# 3_3V_Buck_Schematic.net
KiCad netlist of a schematic drawn in Altium Designer
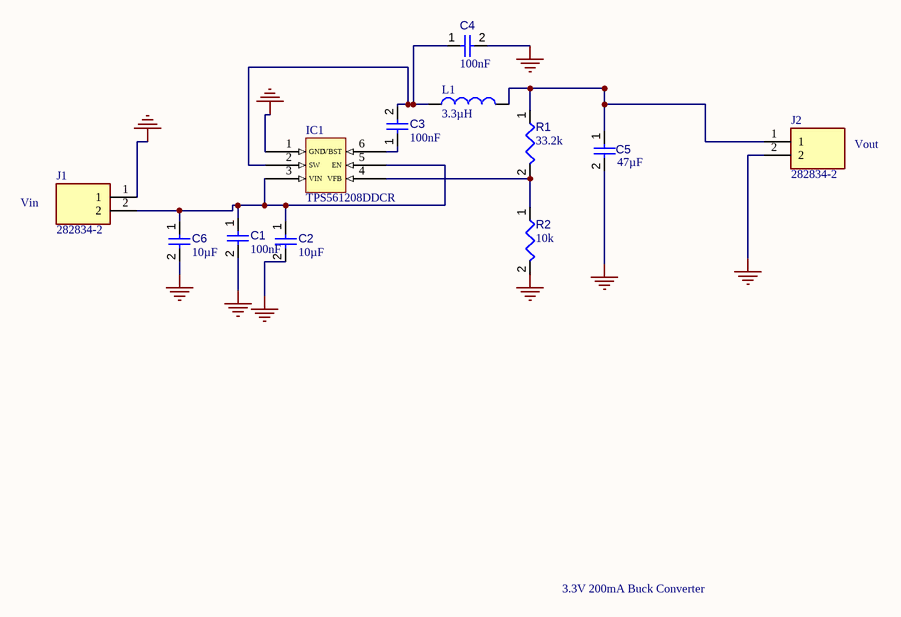
[diagram p0: 3.3V_Buck_Schematic.SchDoc]

(export (version "E")
  (design (tool "Eeschema 10.0.6"))
  (components
    (comp (ref "C1")
      (value "100nF")
      (footprint "CAPC1005X56X25LL10T15")
      (description "Chip Capacitor, 0.1 uF, +/- 5%, 16 V, 0402 (1005 Metric)")
      (fields (field (name "TOLERANCE") "5%") (field (name "Comment") "Capacitor 0.1 uF +/- 5% 16 V 0402"))
      (libsource (lib "Joshua Teele") (part "CAP-NP-2"))
    )
    (comp (ref "C2")
      (value "10µF")
      (footprint "CAPC2012X14N")
      (fields (field (name "Comment") "MSAST21GBB5106MTNA01"))
      (libsource (lib "Joshua Teele") (part "CAP-NP-2"))
    )
    (comp (ref "C3")
      (value "100nF")
      (footprint "CAPC2012X06N")
      (description "0805 100 nF 25V ±10 % Tolerance X7R Surface Mount Multilayer Ceramic Capacitor")
      (fields (field (name "TOLERANCE") "10%") (field (name "Comment") "08053C104KAT2A"))
      (libsource (lib "Joshua Teele") (part "CAP-NP-2"))
    )
    (comp (ref "C4")
      (value "100nF")
      (footprint "CAPC1005X56X25LL10T15")
      (description "Chip Capacitor, 0.1 uF, +/- 5%, 16 V, 0402 (1005 Metric)")
      (fields (field (name "TOLERANCE") "5%") (field (name "Comment") "Capacitor 0.1 uF +/- 5% 16 V 0402"))
      (libsource (lib "Joshua Teele") (part "CAP-NP-2"))
    )
    (comp (ref "C5")
      (value "47µF")
      (footprint "CAPC3225X27N")
      (description "Capacitor: ceramic; MLCC; 47uF; 16V; X5R; ±10%; SMD; 1210; Series: GRM")
      (fields (field (name "VOLTAGE") "16V") (field (name "TOLERANCE") "10%"))
      (libsource (lib "Joshua Teele") (part "CAP-NP-2"))
    )
    (comp (ref "C6")
      (value "10µF")
      (footprint "CAPC2012X14N")
      (fields (field (name "Comment") "MSAST21GBB5106MTNA01"))
      (libsource (lib "Joshua Teele") (part "CAP-NP-2"))
    )
    (comp (ref "IC1")
      (value "TPS561208DDCR")
      (footprint "SOT95P245X110-6N")
      (description "4.5V to 17V Input, 1A Output, Synchronous Step-Down Converter 6-SOT-23-THIN -40 to 125")
      (libsource (lib "Joshua Teele") (part "TPS561208DDCR-Symbol-1"))
    )
    (comp (ref "J1")
      (value "282834-2")
      (footprint "TE_282834-2")
      (description "Terminal Block Connector PCB 2.54 mm 30-16 AWG Green 10 A 150 V M1.6")
      (fields (field (name "MF") "TE Connectivity"))
      (libsource (lib "") (part "282834-2_1"))
    )
    (comp (ref "J2")
      (value "282834-2")
      (footprint "TE_282834-2")
      (description "Terminal Block Connector PCB 2.54 mm 30-16 AWG Green 10 A 150 V M1.6")
      (fields (field (name "MF") "TE Connectivity"))
      (libsource (lib "Joshua Teele") (part "282834-2"))
    )
    (comp (ref "L1")
      (value "3.3µH")
      (footprint "INDP3225X24N")
      (description "Inductor Power Unshielded Wirewound 3.3uH 20% 7.96MHz 15Q-Factor Ferrite 1A 192mOhm DCR 1210 T/R")
      (fields (field (name "TOLERANCE") "20%") (field (name "Comment") "NLCV32T-3R3M-PFR"))
      (libsource (lib "Joshua Teele") (part "IND-2"))
    )
    (comp (ref "R1")
      (value "33.2k")
      (footprint "CAPC2012X07N")
      (description "Res Thick Film 0805 33.2K Ohm 1% 0.125W(1/8W) ±100ppm/°C Molded SMD Punched Carrier T/R")
      (fields (field (name "TOLERANCE") "1%") (field (name "Comment") "ERJ-6ENF3322V"))
      (libsource (lib "Joshua Teele") (part "RES-2"))
    )
    (comp (ref "R2")
      (value "10k")
      (footprint "RESC3216X60X45ML15T20")
      (description "Chip Resistor, 10 KOhm, +/- 1%, 0.25 W, -55 to 155 degC, 1206 (3216 Metric)")
      (fields (field (name "TOLERANCE") "1%") (field (name "POWER") "250mW"))
      (libsource (lib "Joshua Teele") (part "RES-2"))
    )
  )
  (nets
    (net (code "1") (name "GND") (class "Default")
      (node (ref "C1") (pin "2") (pinfunction "2_2") (pintype "passive"))
      (node (ref "C2") (pin "2") (pinfunction "2_2") (pintype "passive"))
      (node (ref "C4") (pin "2") (pinfunction "2_2") (pintype "passive"))
      (node (ref "C5") (pin "2") (pinfunction "2_2") (pintype "passive"))
      (node (ref "C6") (pin "2") (pinfunction "2_2") (pintype "passive"))
      (node (ref "IC1") (pin "1") (pinfunction "GND_1") (pintype "input"))
      (node (ref "J1") (pin "1") (pinfunction "1_1") (pintype "passive"))
      (node (ref "J2") (pin "2") (pinfunction "2_2") (pintype "passive"))
      (node (ref "R2") (pin "2") (pinfunction "2_2") (pintype "passive"))
    )
    (net (code "2") (name "Net-(C5-Pad1)") (class "Default")
      (node (ref "C5") (pin "1") (pinfunction "1_1") (pintype "passive"))
      (node (ref "J2") (pin "1") (pinfunction "1_1") (pintype "passive"))
      (node (ref "L1") (pin "2") (pinfunction "2_2") (pintype "passive"))
      (node (ref "R1") (pin "1") (pinfunction "1_1") (pintype "passive"))
    )
    (net (code "3") (name "Net-(IC1-EN)") (class "Default")
      (node (ref "C1") (pin "1") (pinfunction "1_1") (pintype "passive"))
      (node (ref "C2") (pin "1") (pinfunction "1_1") (pintype "passive"))
      (node (ref "C6") (pin "1") (pinfunction "1_1") (pintype "passive"))
      (node (ref "IC1") (pin "3") (pinfunction "VIN_3") (pintype "input"))
      (node (ref "IC1") (pin "5") (pinfunction "EN_5") (pintype "input"))
      (node (ref "J1") (pin "2") (pinfunction "2_2") (pintype "passive"))
    )
    (net (code "4") (name "Net-(IC1-SW)") (class "Default")
      (node (ref "C3") (pin "2") (pinfunction "2_2") (pintype "passive"))
      (node (ref "C4") (pin "1") (pinfunction "1_1") (pintype "passive"))
      (node (ref "IC1") (pin "2") (pinfunction "SW_2") (pintype "input"))
      (node (ref "L1") (pin "1") (pinfunction "1_1") (pintype "passive"))
    )
    (net (code "5") (name "Net-(IC1-VBST)") (class "Default")
      (node (ref "C3") (pin "1") (pinfunction "1_1") (pintype "passive"))
      (node (ref "IC1") (pin "6") (pinfunction "VBST_6") (pintype "input"))
    )
    (net (code "6") (name "Net-(IC1-VFB)") (class "Default")
      (node (ref "IC1") (pin "4") (pinfunction "VFB_4") (pintype "input"))
      (node (ref "R1") (pin "2") (pinfunction "2_2") (pintype "passive"))
      (node (ref "R2") (pin "1") (pinfunction "1_1") (pintype "passive"))
    )
  )
)
